# G850L.net
KiCad netlist of a schematic drawn in EAGLE
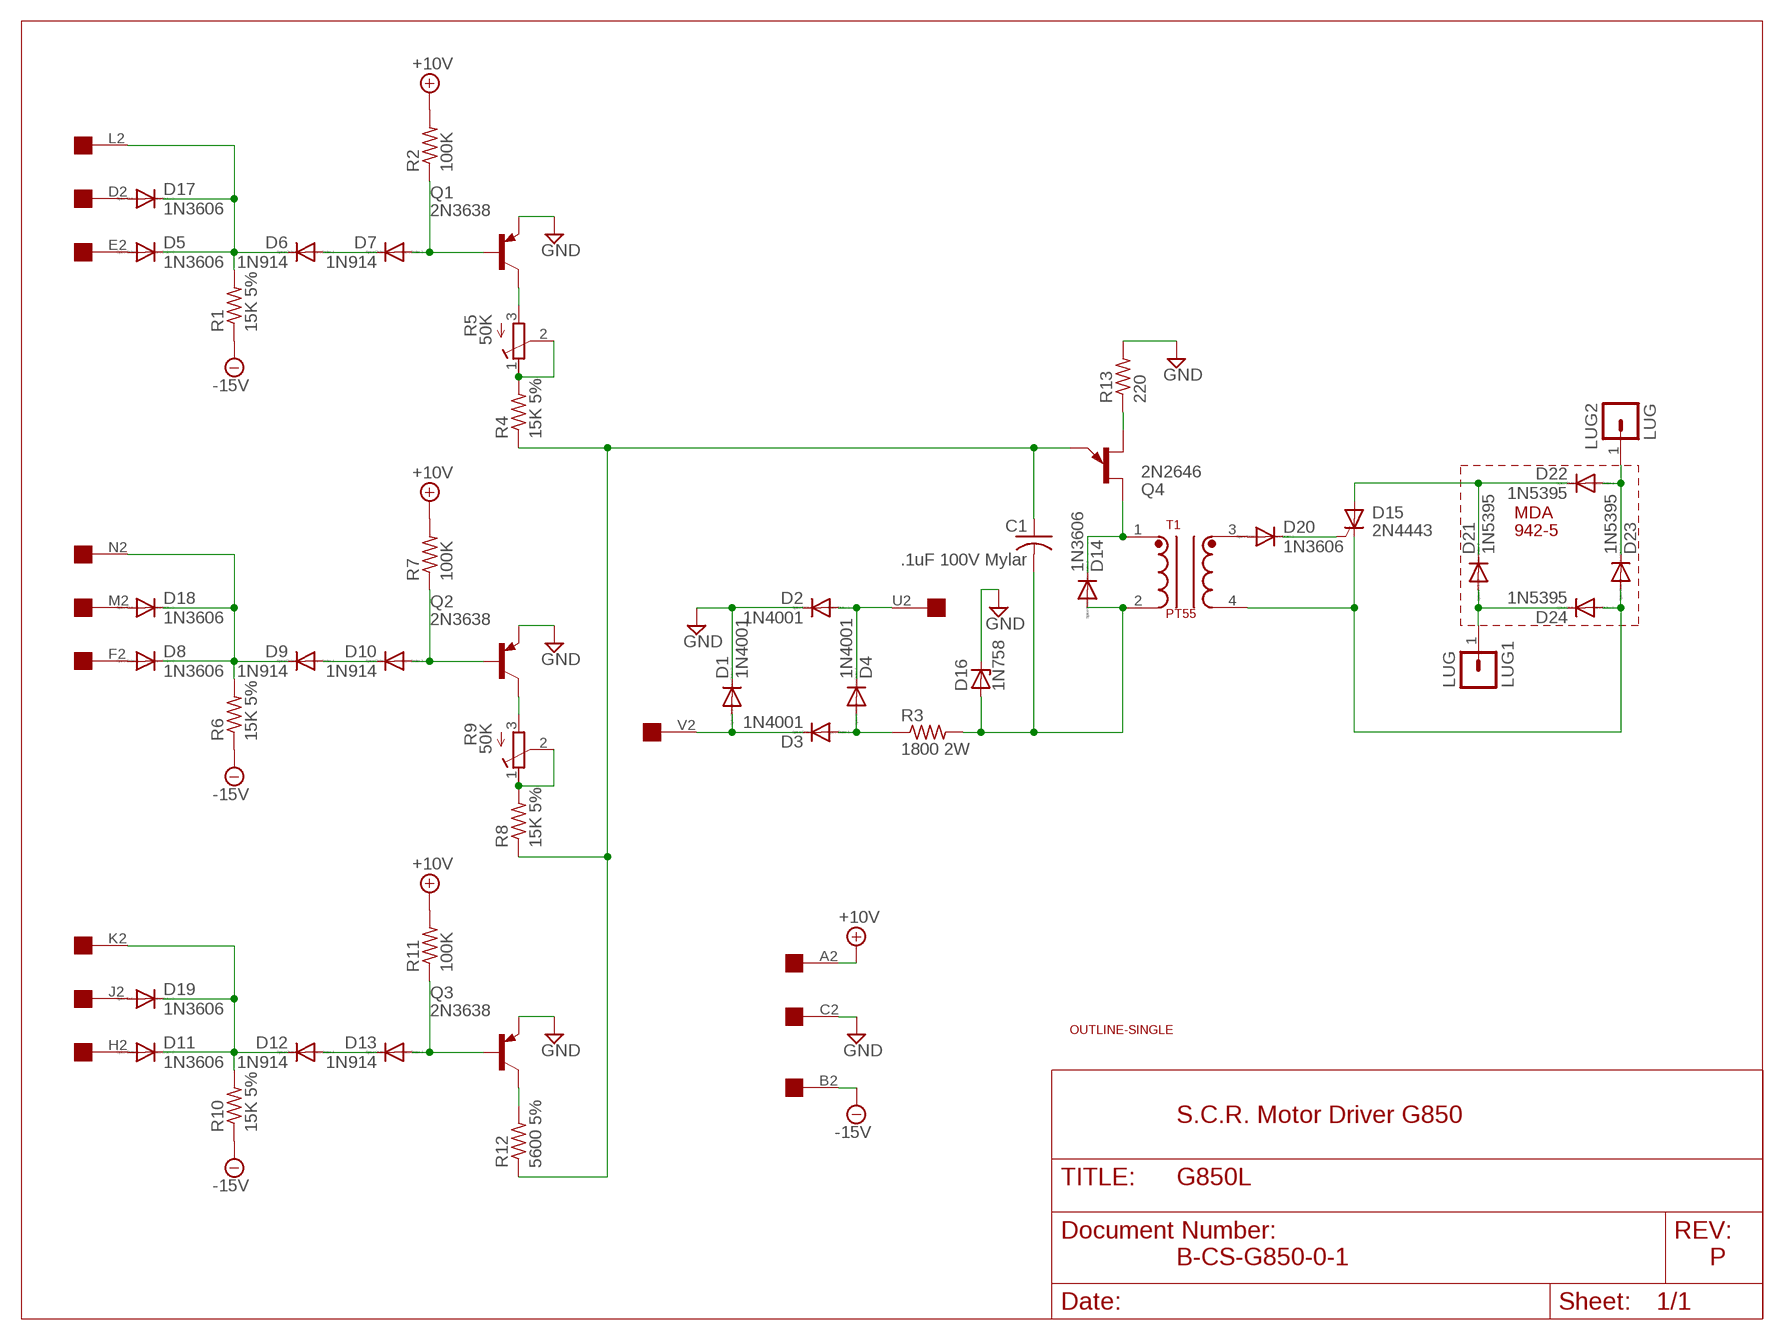
[diagram p0: schematic, sheet 1]

(export (version "E")
  (design (tool "Eeschema 10.0.6"))
  (components
    (comp (ref "C1")
      (value ".1uF 100V Mylar")
      (footprint "eagle-import:C275-093X316")
      (libsource (lib "eagle-import") (part "C-US275-093X316"))
    )
    (comp (ref "D1")
      (value "1N4001")
      (footprint "eagle-import:DO41-10")
      (libsource (lib "eagle-import") (part "1N4004"))
    )
    (comp (ref "D2")
      (value "1N4001")
      (footprint "eagle-import:DO41-10")
      (libsource (lib "eagle-import") (part "1N4004"))
    )
    (comp (ref "D3")
      (value "1N4001")
      (footprint "eagle-import:DO41-10")
      (libsource (lib "eagle-import") (part "1N4004"))
    )
    (comp (ref "D4")
      (value "1N4001")
      (footprint "eagle-import:DO41-10")
      (libsource (lib "eagle-import") (part "1N4004"))
    )
    (comp (ref "D5")
      (value "1N3606")
      (footprint "eagle-import:DO35-10")
      (libsource (lib "eagle-import") (part "1N4148DO35-10"))
    )
    (comp (ref "D6")
      (value "1N914")
      (footprint "eagle-import:DO35-10")
      (libsource (lib "eagle-import") (part "1N4148DO35-10"))
    )
    (comp (ref "D7")
      (value "1N914")
      (footprint "eagle-import:DO35-10")
      (libsource (lib "eagle-import") (part "1N4148DO35-10"))
    )
    (comp (ref "D8")
      (value "1N3606")
      (footprint "eagle-import:DO35-10")
      (libsource (lib "eagle-import") (part "1N4148DO35-10"))
    )
    (comp (ref "D9")
      (value "1N914")
      (footprint "eagle-import:DO35-10")
      (libsource (lib "eagle-import") (part "1N4148DO35-10"))
    )
    (comp (ref "D10")
      (value "1N914")
      (footprint "eagle-import:DO35-10")
      (libsource (lib "eagle-import") (part "1N4148DO35-10"))
    )
    (comp (ref "D11")
      (value "1N3606")
      (footprint "eagle-import:DO35-10")
      (libsource (lib "eagle-import") (part "1N4148DO35-10"))
    )
    (comp (ref "D12")
      (value "1N914")
      (footprint "eagle-import:DO35-10")
      (libsource (lib "eagle-import") (part "1N4148DO35-10"))
    )
    (comp (ref "D13")
      (value "1N914")
      (footprint "eagle-import:DO35-10")
      (libsource (lib "eagle-import") (part "1N4148DO35-10"))
    )
    (comp (ref "D14")
      (value "1N3606")
      (footprint "eagle-import:DO35-10")
      (libsource (lib "eagle-import") (part "1N4148DO35-10"))
    )
    (comp (ref "D15")
      (value "2N4443")
      (footprint "eagle-import:TO220CL")
      (libsource (lib "eagle-import") (part "BT151"))
    )
    (comp (ref "D16")
      (value "1N758")
      (footprint "eagle-import:DO35Z10")
      (libsource (lib "eagle-import") (part "ZENER-DIODEDO35Z10"))
    )
    (comp (ref "D17")
      (value "1N3606")
      (footprint "eagle-import:DO35-10")
      (libsource (lib "eagle-import") (part "1N4148DO35-10"))
    )
    (comp (ref "D18")
      (value "1N3606")
      (footprint "eagle-import:DO35-10")
      (libsource (lib "eagle-import") (part "1N4148DO35-10"))
    )
    (comp (ref "D19")
      (value "1N3606")
      (footprint "eagle-import:DO35-10")
      (libsource (lib "eagle-import") (part "1N4148DO35-10"))
    )
    (comp (ref "D20")
      (value "1N3606")
      (footprint "eagle-import:DO35-10")
      (libsource (lib "eagle-import") (part "1N4148DO35-10"))
    )
    (comp (ref "D21")
      (value "1N5395")
      (footprint "eagle-import:DO41-10")
      (libsource (lib "eagle-import") (part "1N4004"))
    )
    (comp (ref "D22")
      (value "1N5395")
      (footprint "eagle-import:DO41-10")
      (libsource (lib "eagle-import") (part "1N4004"))
    )
    (comp (ref "D23")
      (value "1N5395")
      (footprint "eagle-import:DO41-10")
      (libsource (lib "eagle-import") (part "1N4004"))
    )
    (comp (ref "D24")
      (value "1N5395")
      (footprint "eagle-import:DO41-10")
      (libsource (lib "eagle-import") (part "1N4004"))
    )
    (comp (ref "LUG1")
      (value "LUG")
      (footprint "eagle-import:SPADELUG")
      (libsource (lib "eagle-import") (part "LUG"))
    )
    (comp (ref "LUG2")
      (value "LUG")
      (footprint "eagle-import:SPADELUG")
      (libsource (lib "eagle-import") (part "LUG"))
    )
    (comp (ref "Q1")
      (value "2N3638")
      (footprint "eagle-import:TO39")
      (libsource (lib "eagle-import") (part "2N2904"))
    )
    (comp (ref "Q2")
      (value "2N3638")
      (footprint "eagle-import:TO39")
      (libsource (lib "eagle-import") (part "2N2904"))
    )
    (comp (ref "Q3")
      (value "2N3638")
      (footprint "eagle-import:TO39")
      (libsource (lib "eagle-import") (part "2N2904"))
    )
    (comp (ref "Q4")
      (value "2N2646")
      (footprint "eagle-import:TO72I")
      (libsource (lib "eagle-import") (part "2N2646"))
    )
    (comp (ref "R1")
      (value "15K 5%")
      (footprint "eagle-import:0207_10")
      (libsource (lib "eagle-import") (part "R-US_0207/10"))
    )
    (comp (ref "R2")
      (value "100K")
      (footprint "eagle-import:0207_10")
      (libsource (lib "eagle-import") (part "R-US_0207/10"))
    )
    (comp (ref "R3")
      (value "1800 2W")
      (footprint "eagle-import:P0817_22")
      (libsource (lib "eagle-import") (part "R-US_0817/22"))
    )
    (comp (ref "R4")
      (value "15K 5%")
      (footprint "eagle-import:0207_10")
      (libsource (lib "eagle-import") (part "R-US_0207/10"))
    )
    (comp (ref "R5")
      (value "50K")
      (footprint "eagle-import:3006Y")
      (libsource (lib "eagle-import") (part "275P"))
    )
    (comp (ref "R6")
      (value "15K 5%")
      (footprint "eagle-import:0207_10")
      (libsource (lib "eagle-import") (part "R-US_0207/10"))
    )
    (comp (ref "R7")
      (value "100K")
      (footprint "eagle-import:0207_10")
      (libsource (lib "eagle-import") (part "R-US_0207/10"))
    )
    (comp (ref "R8")
      (value "15K 5%")
      (footprint "eagle-import:0207_10")
      (libsource (lib "eagle-import") (part "R-US_0207/10"))
    )
    (comp (ref "R9")
      (value "50K")
      (footprint "eagle-import:3006Y")
      (libsource (lib "eagle-import") (part "275P"))
    )
    (comp (ref "R10")
      (value "15K 5%")
      (footprint "eagle-import:0207_10")
      (libsource (lib "eagle-import") (part "R-US_0207/10"))
    )
    (comp (ref "R11")
      (value "100K")
      (footprint "eagle-import:0207_10")
      (libsource (lib "eagle-import") (part "R-US_0207/10"))
    )
    (comp (ref "R12")
      (value "5600 5%")
      (footprint "eagle-import:0207_10")
      (libsource (lib "eagle-import") (part "R-US_0207/10"))
    )
    (comp (ref "R13")
      (value "220")
      (footprint "eagle-import:0207_10")
      (libsource (lib "eagle-import") (part "R-US_0207/10"))
    )
    (comp (ref "T1")
      (value "PT55")
      (footprint "eagle-import:PT55")
      (libsource (lib "eagle-import") (part "PT55"))
    )
    (comp (ref "U$1")
      (value "OUTLINE-SINGLE")
      (footprint "eagle-import:SINGLE")
      (libsource (lib "eagle-import") (part "OUTLINE-SINGLE"))
    )
    (comp (ref "U$2")
      (value "EDGE-1")
      (footprint "eagle-import:EDGE-CON1")
      (libsource (lib "eagle-import") (part "EDGE-1"))
    )
  )
  (nets
    (net (code "1") (name "+10V") (class "Default")
      (node (ref "R11") (pin "2") (pinfunction "2_2") (pintype "passive"))
      (node (ref "R2") (pin "2") (pinfunction "2_2") (pintype "passive"))
      (node (ref "R7") (pin "2") (pinfunction "2_2") (pintype "passive"))
      (node (ref "U$2") (pin "A2") (pinfunction "1_A2") (pintype "bidirectional"))
    )
    (net (code "2") (name "-15V") (class "Default")
      (node (ref "R1") (pin "1") (pinfunction "1_1") (pintype "passive"))
      (node (ref "R10") (pin "1") (pinfunction "1_1") (pintype "passive"))
      (node (ref "R6") (pin "1") (pinfunction "1_1") (pintype "passive"))
      (node (ref "U$2") (pin "B2") (pinfunction "1_B2") (pintype "bidirectional"))
    )
    (net (code "3") (name "GND") (class "Default")
      (node (ref "D1") (pin "C") (pinfunction "C_C") (pintype "passive"))
      (node (ref "D16") (pin "C") (pinfunction "C_C") (pintype "passive"))
      (node (ref "D2") (pin "C") (pinfunction "C_C") (pintype "passive"))
      (node (ref "Q1") (pin "1") (pinfunction "E_1") (pintype "passive"))
      (node (ref "Q2") (pin "1") (pinfunction "E_1") (pintype "passive"))
      (node (ref "Q3") (pin "1") (pinfunction "E_1") (pintype "passive"))
      (node (ref "R13") (pin "2") (pinfunction "2_2") (pintype "passive"))
      (node (ref "U$2") (pin "C2") (pinfunction "1_C2") (pintype "bidirectional"))
    )
    (net (code "4") (name "Net-(C1-Pad1)") (class "Default")
      (node (ref "C1") (pin "1") (pinfunction "1_1") (pintype "passive"))
      (node (ref "Q4") (pin "E") (pinfunction "E_E") (pintype "passive"))
      (node (ref "R12") (pin "1") (pinfunction "1_1") (pintype "passive"))
      (node (ref "R4") (pin "1") (pinfunction "1_1") (pintype "passive"))
      (node (ref "R8") (pin "1") (pinfunction "1_1") (pintype "passive"))
    )
    (net (code "5") (name "Net-(D3-PadA)") (class "Default")
      (node (ref "D3") (pin "A") (pinfunction "A_A") (pintype "passive"))
      (node (ref "D4") (pin "A") (pinfunction "A_A") (pintype "passive"))
      (node (ref "R3") (pin "1") (pinfunction "1_1") (pintype "passive"))
    )
    (net (code "6") (name "Net-(D6-PadA)") (class "Default")
      (node (ref "D6") (pin "A") (pinfunction "A_A") (pintype "passive"))
      (node (ref "D7") (pin "C") (pinfunction "C_C") (pintype "passive"))
    )
    (net (code "7") (name "Net-(D10-PadC)") (class "Default")
      (node (ref "D10") (pin "C") (pinfunction "C_C") (pintype "passive"))
      (node (ref "D9") (pin "A") (pinfunction "A_A") (pintype "passive"))
    )
    (net (code "8") (name "Net-(D12-PadA)") (class "Default")
      (node (ref "D12") (pin "A") (pinfunction "A_A") (pintype "passive"))
      (node (ref "D13") (pin "C") (pinfunction "C_C") (pintype "passive"))
    )
    (net (code "9") (name "Net-(D15-PadA)") (class "Default")
      (node (ref "D15") (pin "A") (pinfunction "A_A") (pintype "passive"))
      (node (ref "D21") (pin "C") (pinfunction "C_C") (pintype "passive"))
      (node (ref "D22") (pin "C") (pinfunction "C_C") (pintype "passive"))
    )
    (net (code "10") (name "Net-(D15-PadG)") (class "Default")
      (node (ref "D15") (pin "G") (pinfunction "G_G") (pintype "passive"))
      (node (ref "D20") (pin "C") (pinfunction "C_C") (pintype "passive"))
    )
    (net (code "11") (name "Net-(D21-PadA)") (class "Default")
      (node (ref "D21") (pin "A") (pinfunction "A_A") (pintype "passive"))
      (node (ref "D24") (pin "C") (pinfunction "C_C") (pintype "passive"))
      (node (ref "LUG1") (pin "1") (pinfunction "1_1") (pintype "passive"))
    )
    (net (code "12") (name "Net-(D22-PadA)") (class "Default")
      (node (ref "D22") (pin "A") (pinfunction "A_A") (pintype "passive"))
      (node (ref "D23") (pin "C") (pinfunction "C_C") (pintype "passive"))
      (node (ref "LUG2") (pin "1") (pinfunction "1_1") (pintype "passive"))
    )
    (net (code "13") (name "Net-(Q1-B)") (class "Default")
      (node (ref "D7") (pin "A") (pinfunction "A_A") (pintype "passive"))
      (node (ref "Q1") (pin "2") (pinfunction "B_2") (pintype "passive"))
      (node (ref "R2") (pin "1") (pinfunction "1_1") (pintype "passive"))
    )
    (net (code "14") (name "Net-(Q1-C)") (class "Default")
      (node (ref "Q1") (pin "3") (pinfunction "C_3") (pintype "passive"))
      (node (ref "R5") (pin "3") (pinfunction "E_3") (pintype "passive"))
    )
    (net (code "15") (name "Net-(Q2-B)") (class "Default")
      (node (ref "D10") (pin "A") (pinfunction "A_A") (pintype "passive"))
      (node (ref "Q2") (pin "2") (pinfunction "B_2") (pintype "passive"))
      (node (ref "R7") (pin "1") (pinfunction "1_1") (pintype "passive"))
    )
    (net (code "16") (name "Net-(Q2-C)") (class "Default")
      (node (ref "Q2") (pin "3") (pinfunction "C_3") (pintype "passive"))
      (node (ref "R9") (pin "3") (pinfunction "E_3") (pintype "passive"))
    )
    (net (code "17") (name "Net-(Q3-B)") (class "Default")
      (node (ref "D13") (pin "A") (pinfunction "A_A") (pintype "passive"))
      (node (ref "Q3") (pin "2") (pinfunction "B_2") (pintype "passive"))
      (node (ref "R11") (pin "1") (pinfunction "1_1") (pintype "passive"))
    )
    (net (code "18") (name "Net-(Q3-C)") (class "Default")
      (node (ref "Q3") (pin "3") (pinfunction "C_3") (pintype "passive"))
      (node (ref "R12") (pin "2") (pinfunction "2_2") (pintype "passive"))
    )
    (net (code "19") (name "Net-(Q4-PadB1)") (class "Default")
      (node (ref "Q4") (pin "B1") (pinfunction "B1_B1") (pintype "passive"))
      (node (ref "R13") (pin "1") (pinfunction "1_1") (pintype "passive"))
    )
    (net (code "20") (name "Net-(R5-A)") (class "Default")
      (node (ref "R4") (pin "2") (pinfunction "2_2") (pintype "passive"))
      (node (ref "R5") (pin "1") (pinfunction "A_1") (pintype "passive"))
      (node (ref "R5") (pin "2") (pinfunction "S_2") (pintype "passive"))
    )
    (net (code "21") (name "Net-(R9-A)") (class "Default")
      (node (ref "R8") (pin "2") (pinfunction "2_2") (pintype "passive"))
      (node (ref "R9") (pin "1") (pinfunction "A_1") (pintype "passive"))
      (node (ref "R9") (pin "2") (pinfunction "S_2") (pintype "passive"))
    )
    (net (code "22") (name "Net-(T1-P$2)") (class "Default")
      (node (ref "D14") (pin "C") (pinfunction "C_C") (pintype "passive"))
      (node (ref "Q4") (pin "B2") (pinfunction "B2_B2") (pintype "passive"))
      (node (ref "T1") (pin "1") (pinfunction "P$2_1") (pintype "passive"))
    )
    (net (code "23") (name "Net-(T1-P$4)") (class "Default")
      (node (ref "D20") (pin "A") (pinfunction "A_A") (pintype "passive"))
      (node (ref "T1") (pin "3") (pinfunction "P$4_3") (pintype "passive"))
    )
    (net (code "24") (name "Net-(T1-P$5)") (class "Default")
      (node (ref "D15") (pin "C") (pinfunction "C_C") (pintype "passive"))
      (node (ref "D23") (pin "A") (pinfunction "A_A") (pintype "passive"))
      (node (ref "D24") (pin "A") (pinfunction "A_A") (pintype "passive"))
      (node (ref "T1") (pin "4") (pinfunction "P$5_4") (pintype "passive"))
    )
    (net (code "25") (name "Net-(T1-P$7)") (class "Default")
      (node (ref "C1") (pin "2") (pinfunction "2_2") (pintype "passive"))
      (node (ref "D14") (pin "A") (pinfunction "A_A") (pintype "passive"))
      (node (ref "D16") (pin "A") (pinfunction "A_A") (pintype "passive"))
      (node (ref "R3") (pin "2") (pinfunction "2_2") (pintype "passive"))
      (node (ref "T1") (pin "2") (pinfunction "P$7_2") (pintype "passive"))
    )
    (net (code "26") (name "Net-(U$2D-1)") (class "Default")
      (node (ref "D17") (pin "A") (pinfunction "A_A") (pintype "passive"))
      (node (ref "U$2") (pin "D2") (pinfunction "1_D2") (pintype "bidirectional"))
    )
    (net (code "27") (name "Net-(U$2E-1)") (class "Default")
      (node (ref "D5") (pin "A") (pinfunction "A_A") (pintype "passive"))
      (node (ref "U$2") (pin "E2") (pinfunction "1_E2") (pintype "bidirectional"))
    )
    (net (code "28") (name "Net-(U$2F-1)") (class "Default")
      (node (ref "D8") (pin "A") (pinfunction "A_A") (pintype "passive"))
      (node (ref "U$2") (pin "F2") (pinfunction "1_F2") (pintype "bidirectional"))
    )
    (net (code "29") (name "Net-(U$2G-1)") (class "Default")
      (node (ref "D11") (pin "A") (pinfunction "A_A") (pintype "passive"))
      (node (ref "U$2") (pin "H2") (pinfunction "1_H2") (pintype "bidirectional"))
    )
    (net (code "30") (name "Net-(U$2H-1)") (class "Default")
      (node (ref "D19") (pin "A") (pinfunction "A_A") (pintype "passive"))
      (node (ref "U$2") (pin "J2") (pinfunction "1_J2") (pintype "bidirectional"))
    )
    (net (code "31") (name "Net-(U$2I-1)") (class "Default")
      (node (ref "D11") (pin "C") (pinfunction "C_C") (pintype "passive"))
      (node (ref "D12") (pin "C") (pinfunction "C_C") (pintype "passive"))
      (node (ref "D19") (pin "C") (pinfunction "C_C") (pintype "passive"))
      (node (ref "R10") (pin "2") (pinfunction "2_2") (pintype "passive"))
      (node (ref "U$2") (pin "K2") (pinfunction "1_K2") (pintype "bidirectional"))
    )
    (net (code "32") (name "Net-(U$2J-1)") (class "Default")
      (node (ref "D17") (pin "C") (pinfunction "C_C") (pintype "passive"))
      (node (ref "D5") (pin "C") (pinfunction "C_C") (pintype "passive"))
      (node (ref "D6") (pin "C") (pinfunction "C_C") (pintype "passive"))
      (node (ref "R1") (pin "2") (pinfunction "2_2") (pintype "passive"))
      (node (ref "U$2") (pin "L2") (pinfunction "1_L2") (pintype "bidirectional"))
    )
    (net (code "33") (name "Net-(U$2K-1)") (class "Default")
      (node (ref "D18") (pin "A") (pinfunction "A_A") (pintype "passive"))
      (node (ref "U$2") (pin "M2") (pinfunction "1_M2") (pintype "bidirectional"))
    )
    (net (code "34") (name "Net-(U$2L-1)") (class "Default")
      (node (ref "D18") (pin "C") (pinfunction "C_C") (pintype "passive"))
      (node (ref "D8") (pin "C") (pinfunction "C_C") (pintype "passive"))
      (node (ref "D9") (pin "C") (pinfunction "C_C") (pintype "passive"))
      (node (ref "R6") (pin "2") (pinfunction "2_2") (pintype "passive"))
      (node (ref "U$2") (pin "N2") (pinfunction "1_N2") (pintype "bidirectional"))
    )
    (net (code "35") (name "Net-(U$2Q-1)") (class "Default")
      (node (ref "D2") (pin "A") (pinfunction "A_A") (pintype "passive"))
      (node (ref "D4") (pin "C") (pinfunction "C_C") (pintype "passive"))
      (node (ref "U$2") (pin "U2") (pinfunction "1_U2") (pintype "bidirectional"))
    )
    (net (code "36") (name "Net-(U$2R-1)") (class "Default")
      (node (ref "D1") (pin "A") (pinfunction "A_A") (pintype "passive"))
      (node (ref "D3") (pin "C") (pinfunction "C_C") (pintype "passive"))
      (node (ref "U$2") (pin "V2") (pinfunction "1_V2") (pintype "bidirectional"))
    )
  )
)
